# HW1_73.net
KiCad netlist of a schematic drawn in EasyEDA
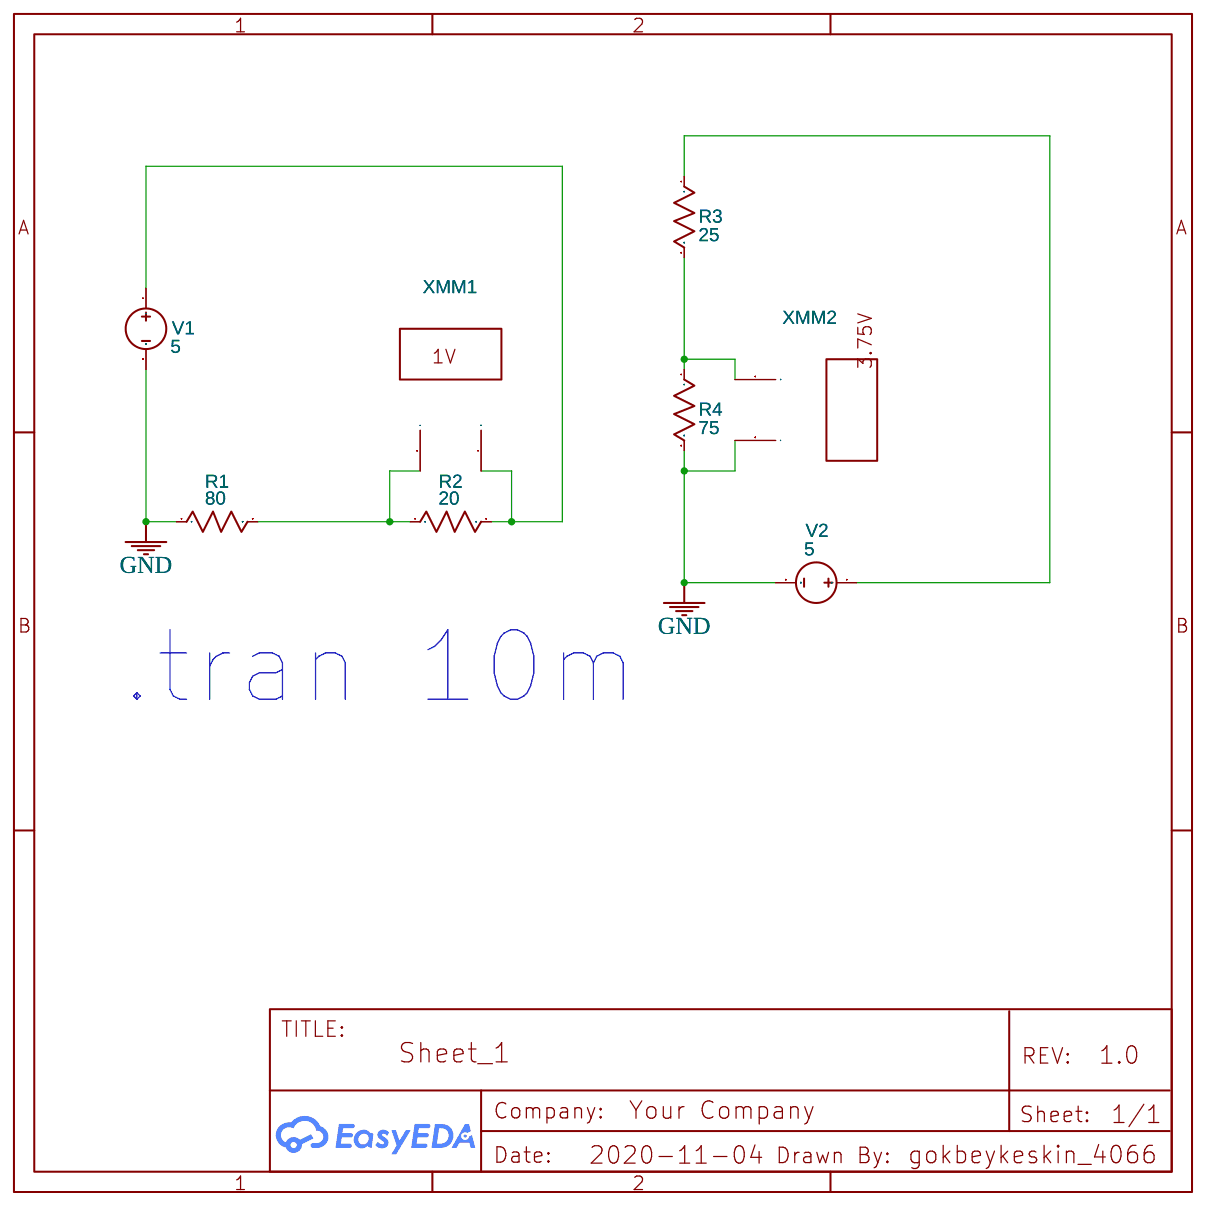
[diagram p0: schematic sheet]

(export (version "E")
  (design (tool "Eeschema 10.0.6"))
  (components
    (comp (ref "R1") (value "80") (libsource (lib "") (part "Resistor_US")))
    (comp (ref "R2") (value "20") (libsource (lib "") (part "Resistor_US")))
    (comp (ref "R3") (value "25") (libsource (lib "") (part "Resistor_US_1")))
    (comp (ref "R4") (value "75") (libsource (lib "") (part "Resistor_US_1")))
    (comp (ref "V1") (value "5") (libsource (lib "") (part "VDC_1")))
    (comp (ref "V2") (value "5") (libsource (lib "") (part "VDC")))
    (comp (ref "XMM1") (value "Multimeter") (libsource (lib "") (part "MULTIMETER_1")))
    (comp (ref "XMM2") (value "Multimeter") (libsource (lib "") (part "MULTIMETER")))
  )
  (nets
    (net (code "1") (name "GND") (class "Default")
      (node (ref "R1") (pin "1") (pinfunction "1_1") (pintype "unspecified"))
      (node (ref "R4") (pin "2") (pinfunction "2_2") (pintype "unspecified"))
      (node (ref "V1") (pin "2") (pinfunction "2_2") (pintype "unspecified"))
      (node (ref "V2") (pin "2") (pinfunction "2_2") (pintype "unspecified"))
      (node (ref "XMM2") (pin "2") (pinfunction "I_2") (pintype "unspecified"))
    )
    (net (code "2") (name "Net-(R3-Pad1)") (class "Default")
      (node (ref "R3") (pin "1") (pinfunction "1_1") (pintype "unspecified"))
      (node (ref "V2") (pin "1") (pinfunction "1_1") (pintype "unspecified"))
    )
    (net (code "3") (name "Net-(XMM1-+)") (class "Default")
      (node (ref "R2") (pin "2") (pinfunction "2_2") (pintype "unspecified"))
      (node (ref "V1") (pin "1") (pinfunction "1_1") (pintype "unspecified"))
      (node (ref "XMM1") (pin "1") (pinfunction "+_1") (pintype "unspecified"))
    )
    (net (code "4") (name "Net-(XMM1-I)") (class "Default")
      (node (ref "R1") (pin "2") (pinfunction "2_2") (pintype "unspecified"))
      (node (ref "R2") (pin "1") (pinfunction "1_1") (pintype "unspecified"))
      (node (ref "XMM1") (pin "2") (pinfunction "I_2") (pintype "unspecified"))
    )
    (net (code "5") (name "Net-(XMM2-+)") (class "Default")
      (node (ref "R3") (pin "2") (pinfunction "2_2") (pintype "unspecified"))
      (node (ref "R4") (pin "1") (pinfunction "1_1") (pintype "unspecified"))
      (node (ref "XMM2") (pin "1") (pinfunction "+_1") (pintype "unspecified"))
    )
  )
)
